# polar_bear.net
KiCad netlist of a schematic drawn in EAGLE
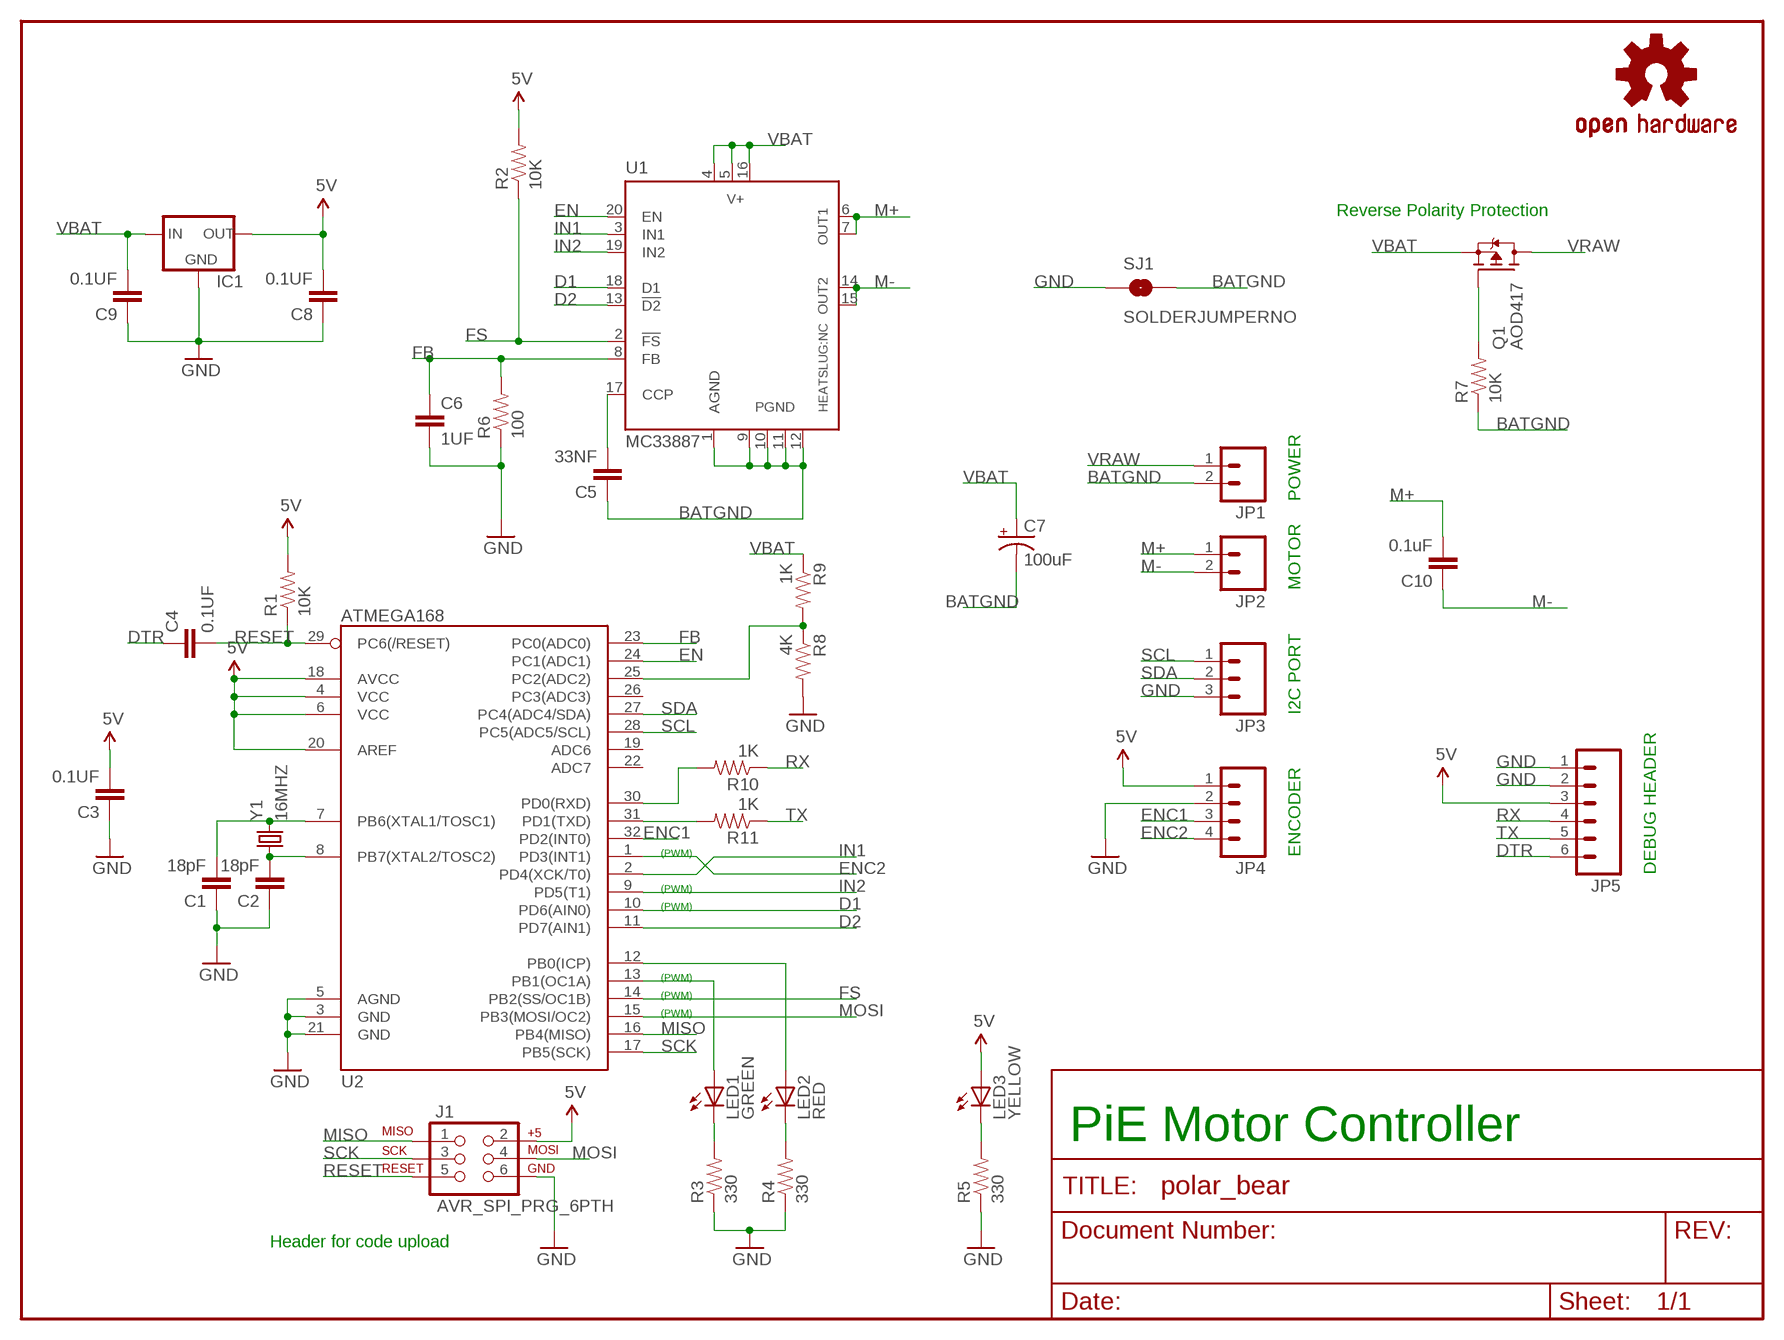
[diagram p0: schematic, sheet 1]

(export (version "E")
  (design (tool "Eeschema 10.0.6"))
  (components
    (comp (ref "C1")
      (value "18pF")
      (footprint "eagle-import:0805")
      (libsource (lib "eagle-import") (part "CAP0805"))
    )
    (comp (ref "C2")
      (value "18pF")
      (footprint "eagle-import:0805")
      (libsource (lib "eagle-import") (part "CAP0805"))
    )
    (comp (ref "C3")
      (value "0.1UF")
      (footprint "eagle-import:0805")
      (libsource (lib "eagle-import") (part "CAP0805"))
    )
    (comp (ref "C4")
      (value "0.1UF")
      (footprint "eagle-import:0805")
      (libsource (lib "eagle-import") (part "CAP0805"))
    )
    (comp (ref "C5")
      (value "33NF")
      (footprint "eagle-import:0805")
      (libsource (lib "eagle-import") (part "CAP0805"))
    )
    (comp (ref "C6")
      (value "1UF")
      (footprint "eagle-import:0805")
      (libsource (lib "eagle-import") (part "CAP0805"))
    )
    (comp (ref "C7")
      (value "100uF")
      (footprint "eagle-import:CPOL-RADIAL-100UF-25V")
      (libsource (lib "eagle-import") (part "CAP_POLPTH1"))
    )
    (comp (ref "C8")
      (value "0.1UF")
      (footprint "eagle-import:0805")
      (libsource (lib "eagle-import") (part "CAP0805"))
    )
    (comp (ref "C9")
      (value "0.1UF")
      (footprint "eagle-import:0805")
      (libsource (lib "eagle-import") (part "CAP0805"))
    )
    (comp (ref "C10")
      (value "0.1uF")
      (footprint "eagle-import:0805")
      (libsource (lib "eagle-import") (part "CAP0805"))
    )
    (comp (ref "IC1")
      (value "V_REG_78XXTO-92")
      (footprint "eagle-import:TO-92")
      (libsource (lib "eagle-import") (part "V_REG_78XXTO-92"))
    )
    (comp (ref "J1")
      (value "AVR_SPI_PRG_6PTH")
      (footprint "eagle-import:2X3")
      (libsource (lib "eagle-import") (part "AVR_SPI_PRG_6PTH"))
    )
    (comp (ref "JP1")
      (value "M02PTH4")
      (footprint "eagle-import:1X02_XTRA_BIG")
      (libsource (lib "eagle-import") (part "M02PTH4"))
    )
    (comp (ref "JP2")
      (value "M02PTH4")
      (footprint "eagle-import:1X02_XTRA_BIG")
      (libsource (lib "eagle-import") (part "M02PTH4"))
    )
    (comp (ref "JP3")
      (value "M03POLAR")
      (footprint "eagle-import:MOLEX-1X3")
      (libsource (lib "eagle-import") (part "M03POLAR"))
    )
    (comp (ref "JP4")
      (value "M04POLAR")
      (footprint "eagle-import:MOLEX-1X4")
      (libsource (lib "eagle-import") (part "M04POLAR"))
    )
    (comp (ref "JP5")
      (value "M06SIP")
      (footprint "eagle-import:1X06")
      (libsource (lib "eagle-import") (part "M06SIP"))
    )
    (comp (ref "LED1")
      (value "GREEN")
      (footprint "eagle-import:LED-1206")
      (libsource (lib "eagle-import") (part "LED1206"))
    )
    (comp (ref "LED2")
      (value "RED")
      (footprint "eagle-import:LED-1206")
      (libsource (lib "eagle-import") (part "LED1206"))
    )
    (comp (ref "LED3")
      (value "YELLOW")
      (footprint "eagle-import:LED-1206")
      (libsource (lib "eagle-import") (part "LED1206"))
    )
    (comp (ref "Q1")
      (value "AOD417")
      (footprint "eagle-import:TO252")
      (libsource (lib "eagle-import") (part "AOD417"))
    )
    (comp (ref "R1")
      (value "10K")
      (footprint "eagle-import:0805")
      (libsource (lib "eagle-import") (part "RESISTOR0805-RES"))
    )
    (comp (ref "R2")
      (value "10K")
      (footprint "eagle-import:0805")
      (libsource (lib "eagle-import") (part "RESISTOR0805-RES"))
    )
    (comp (ref "R3")
      (value "330")
      (footprint "eagle-import:0805")
      (libsource (lib "eagle-import") (part "RESISTOR0805-RES"))
    )
    (comp (ref "R4")
      (value "330")
      (footprint "eagle-import:0805")
      (libsource (lib "eagle-import") (part "RESISTOR0805-RES"))
    )
    (comp (ref "R5")
      (value "330")
      (footprint "eagle-import:0805")
      (libsource (lib "eagle-import") (part "RESISTOR0805-RES"))
    )
    (comp (ref "R6")
      (value "100")
      (footprint "eagle-import:0805")
      (libsource (lib "eagle-import") (part "RESISTOR0805-RES"))
    )
    (comp (ref "R7")
      (value "10K")
      (footprint "eagle-import:0805")
      (libsource (lib "eagle-import") (part "RESISTOR0805-RES"))
    )
    (comp (ref "R8")
      (value "4K")
      (footprint "eagle-import:0805")
      (libsource (lib "eagle-import") (part "RESISTOR0805-RES"))
    )
    (comp (ref "R9")
      (value "1K")
      (footprint "eagle-import:0805")
      (libsource (lib "eagle-import") (part "RESISTOR0805-RES"))
    )
    (comp (ref "R10")
      (value "1K")
      (footprint "eagle-import:0805")
      (libsource (lib "eagle-import") (part "RESISTOR0805-RES"))
    )
    (comp (ref "R11")
      (value "1K")
      (footprint "eagle-import:0805")
      (libsource (lib "eagle-import") (part "RESISTOR0805-RES"))
    )
    (comp (ref "SJ1")
      (value "SOLDERJUMPERNO")
      (footprint "eagle-import:SJ_2S-NO")
      (libsource (lib "eagle-import") (part "SOLDERJUMPERNO"))
    )
    (comp (ref "U$12")
      (value "OSHW-LOGOS")
      (footprint "eagle-import:OSHW-LOGO-S")
      (libsource (lib "eagle-import") (part "OSHW-LOGOS"))
    )
    (comp (ref "U1")
      (value "MC33887")
      (footprint "eagle-import:HSOP-20")
      (libsource (lib "eagle-import") (part "MC33887"))
    )
    (comp (ref "U2")
      (value "ATMEGA168")
      (footprint "eagle-import:TQFP32-08")
      (libsource (lib "eagle-import") (part "ATMEGA168"))
    )
    (comp (ref "Y1")
      (value "16MHZ")
      (footprint "eagle-import:HC49US")
      (libsource (lib "eagle-import") (part "CRYSTALHC49US"))
    )
  )
  (nets
    (net (code "1") (name "/BATGND") (class "Default")
      (node (ref "C5") (pin "1") (pinfunction "1_1") (pintype "passive"))
      (node (ref "C7") (pin "2") (pinfunction "-_2") (pintype "passive"))
      (node (ref "JP1") (pin "2") (pinfunction "2_2") (pintype "passive"))
      (node (ref "R7") (pin "1") (pinfunction "1_1") (pintype "passive"))
      (node (ref "SJ1") (pin "2") (pinfunction "2_2") (pintype "passive"))
      (node (ref "U1") (pin "1") (pinfunction "AGND_1") (pintype "power_in"))
      (node (ref "U1") (pin "10") (pinfunction "PGND_10") (pintype "power_in"))
      (node (ref "U1") (pin "11") (pinfunction "PGND_11") (pintype "power_in"))
      (node (ref "U1") (pin "12") (pinfunction "PGND_12") (pintype "power_in"))
      (node (ref "U1") (pin "9") (pinfunction "PGND_9") (pintype "power_in"))
    )
    (net (code "2") (name "/D1") (class "Default")
      (node (ref "U1") (pin "18") (pinfunction "D1_18") (pintype "input"))
      (node (ref "U2") (pin "10") (pinfunction "PD6(AIN0)_10") (pintype "bidirectional"))
    )
    (net (code "3") (name "/D2") (class "Default")
      (node (ref "U1") (pin "13") (pinfunction "~{D2}_13") (pintype "input"))
      (node (ref "U2") (pin "11") (pinfunction "PD7(AIN1)_11") (pintype "bidirectional"))
    )
    (net (code "4") (name "/DTR") (class "Default")
      (node (ref "C4") (pin "1") (pinfunction "1_1") (pintype "passive"))
      (node (ref "JP5") (pin "6") (pinfunction "6_6") (pintype "passive"))
    )
    (net (code "5") (name "/EN") (class "Default")
      (node (ref "U1") (pin "20") (pinfunction "EN_20") (pintype "input"))
      (node (ref "U2") (pin "24") (pinfunction "PC1(ADC1)_24") (pintype "bidirectional"))
    )
    (net (code "6") (name "/ENC1") (class "Default")
      (node (ref "JP4") (pin "3") (pinfunction "3_3") (pintype "passive"))
      (node (ref "U2") (pin "32") (pinfunction "PD2(INT0)_32") (pintype "bidirectional"))
    )
    (net (code "7") (name "/ENC2") (class "Default")
      (node (ref "JP4") (pin "4") (pinfunction "4_4") (pintype "passive"))
      (node (ref "U2") (pin "1") (pinfunction "PD3(INT1)_1") (pintype "bidirectional"))
    )
    (net (code "8") (name "/FB") (class "Default")
      (node (ref "C6") (pin "1") (pinfunction "1_1") (pintype "passive"))
      (node (ref "R6") (pin "2") (pinfunction "2_2") (pintype "passive"))
      (node (ref "U1") (pin "8") (pinfunction "FB_8") (pintype "output"))
      (node (ref "U2") (pin "23") (pinfunction "PC0(ADC0)_23") (pintype "bidirectional"))
    )
    (net (code "9") (name "/FS") (class "Default")
      (node (ref "R2") (pin "1") (pinfunction "1_1") (pintype "passive"))
      (node (ref "U1") (pin "2") (pinfunction "~{FS}_2") (pintype "open_collector"))
      (node (ref "U2") (pin "14") (pinfunction "PB2(SS/OC1B)_14") (pintype "bidirectional"))
    )
    (net (code "10") (name "/IN1") (class "Default")
      (node (ref "U1") (pin "3") (pinfunction "IN1_3") (pintype "input"))
      (node (ref "U2") (pin "2") (pinfunction "PD4(XCK/T0)_2") (pintype "bidirectional"))
    )
    (net (code "11") (name "/IN2") (class "Default")
      (node (ref "U1") (pin "19") (pinfunction "IN2_19") (pintype "input"))
      (node (ref "U2") (pin "9") (pinfunction "PD5(T1)_9") (pintype "bidirectional"))
    )
    (net (code "12") (name "/M+") (class "Default")
      (node (ref "C10") (pin "2") (pinfunction "2_2") (pintype "passive"))
      (node (ref "JP2") (pin "1") (pinfunction "1_1") (pintype "passive"))
      (node (ref "U1") (pin "6") (pinfunction "OUT1_6") (pintype "output"))
      (node (ref "U1") (pin "7") (pinfunction "OUT1_7") (pintype "output"))
    )
    (net (code "13") (name "/M-") (class "Default")
      (node (ref "C10") (pin "1") (pinfunction "1_1") (pintype "passive"))
      (node (ref "JP2") (pin "2") (pinfunction "2_2") (pintype "passive"))
      (node (ref "U1") (pin "14") (pinfunction "OUT2_14") (pintype "output"))
      (node (ref "U1") (pin "15") (pinfunction "OUT2_15") (pintype "output"))
    )
    (net (code "14") (name "/MISO") (class "Default")
      (node (ref "J1") (pin "1") (pinfunction "1_1") (pintype "passive"))
      (node (ref "U2") (pin "16") (pinfunction "PB4(MISO)_16") (pintype "bidirectional"))
    )
    (net (code "15") (name "/MOSI") (class "Default")
      (node (ref "J1") (pin "4") (pinfunction "4_4") (pintype "passive"))
      (node (ref "U2") (pin "15") (pinfunction "PB3(MOSI/OC2)_15") (pintype "bidirectional"))
    )
    (net (code "16") (name "/RESET") (class "Default")
      (node (ref "C4") (pin "2") (pinfunction "2_2") (pintype "passive"))
      (node (ref "J1") (pin "5") (pinfunction "5_5") (pintype "passive"))
      (node (ref "R1") (pin "1") (pinfunction "1_1") (pintype "passive"))
      (node (ref "U2") (pin "29") (pinfunction "PC6(/RESET)_29") (pintype "bidirectional"))
    )
    (net (code "17") (name "/RX") (class "Default")
      (node (ref "JP5") (pin "4") (pinfunction "4_4") (pintype "passive"))
      (node (ref "R10") (pin "1") (pinfunction "1_1") (pintype "passive"))
    )
    (net (code "18") (name "/SCK") (class "Default")
      (node (ref "J1") (pin "3") (pinfunction "3_3") (pintype "passive"))
      (node (ref "U2") (pin "17") (pinfunction "PB5(SCK)_17") (pintype "bidirectional"))
    )
    (net (code "19") (name "/SCL") (class "Default")
      (node (ref "JP3") (pin "1") (pinfunction "1_1") (pintype "passive"))
      (node (ref "U2") (pin "28") (pinfunction "PC5(ADC5/SCL)_28") (pintype "bidirectional"))
    )
    (net (code "20") (name "/SDA") (class "Default")
      (node (ref "JP3") (pin "2") (pinfunction "2_2") (pintype "passive"))
      (node (ref "U2") (pin "27") (pinfunction "PC4(ADC4/SDA)_27") (pintype "bidirectional"))
    )
    (net (code "21") (name "/TX") (class "Default")
      (node (ref "JP5") (pin "5") (pinfunction "5_5") (pintype "passive"))
      (node (ref "R11") (pin "1") (pinfunction "1_1") (pintype "passive"))
    )
    (net (code "22") (name "/VBAT") (class "Default")
      (node (ref "C7") (pin "1") (pinfunction "+_1") (pintype "passive"))
      (node (ref "C9") (pin "2") (pinfunction "2_2") (pintype "passive"))
      (node (ref "IC1") (pin "2") (pinfunction "IN_2") (pintype "input"))
      (node (ref "Q1") (pin "2") (pinfunction "S_2") (pintype "passive"))
      (node (ref "R9") (pin "1") (pinfunction "1_1") (pintype "passive"))
      (node (ref "U1") (pin "16") (pinfunction "V+_16") (pintype "power_in"))
      (node (ref "U1") (pin "4") (pinfunction "V+_4") (pintype "power_in"))
      (node (ref "U1") (pin "5") (pinfunction "V+_5") (pintype "power_in"))
    )
    (net (code "23") (name "/VRAW") (class "Default")
      (node (ref "JP1") (pin "1") (pinfunction "1_1") (pintype "passive"))
      (node (ref "Q1") (pin "3") (pinfunction "D_3") (pintype "passive"))
    )
    (net (code "24") (name "5V") (class "Default")
      (node (ref "C3") (pin "2") (pinfunction "2_2") (pintype "passive"))
      (node (ref "C8") (pin "2") (pinfunction "2_2") (pintype "passive"))
      (node (ref "IC1") (pin "3") (pinfunction "OUT_3") (pintype "output"))
      (node (ref "J1") (pin "2") (pinfunction "2_2") (pintype "passive"))
      (node (ref "JP4") (pin "1") (pinfunction "1_1") (pintype "passive"))
      (node (ref "JP5") (pin "3") (pinfunction "3_3") (pintype "passive"))
      (node (ref "LED3") (pin "A") (pinfunction "A_A") (pintype "passive"))
      (node (ref "R1") (pin "2") (pinfunction "2_2") (pintype "passive"))
      (node (ref "R2") (pin "2") (pinfunction "2_2") (pintype "passive"))
      (node (ref "U2") (pin "18") (pinfunction "AVCC_18") (pintype "bidirectional"))
      (node (ref "U2") (pin "20") (pinfunction "AREF_20") (pintype "bidirectional"))
      (node (ref "U2") (pin "4") (pinfunction "VCC_4") (pintype "bidirectional"))
      (node (ref "U2") (pin "6") (pinfunction "VCC_6") (pintype "bidirectional"))
    )
    (net (code "25") (name "GND") (class "Default")
      (node (ref "C1") (pin "1") (pinfunction "1_1") (pintype "passive"))
      (node (ref "C2") (pin "1") (pinfunction "1_1") (pintype "passive"))
      (node (ref "C3") (pin "1") (pinfunction "1_1") (pintype "passive"))
      (node (ref "C6") (pin "2") (pinfunction "2_2") (pintype "passive"))
      (node (ref "C8") (pin "1") (pinfunction "1_1") (pintype "passive"))
      (node (ref "C9") (pin "1") (pinfunction "1_1") (pintype "passive"))
      (node (ref "IC1") (pin "1") (pinfunction "GND_1") (pintype "input"))
      (node (ref "J1") (pin "6") (pinfunction "6_6") (pintype "passive"))
      (node (ref "JP3") (pin "3") (pinfunction "3_3") (pintype "passive"))
      (node (ref "JP4") (pin "2") (pinfunction "2_2") (pintype "passive"))
      (node (ref "JP5") (pin "1") (pinfunction "1_1") (pintype "passive"))
      (node (ref "JP5") (pin "2") (pinfunction "2_2") (pintype "passive"))
      (node (ref "R3") (pin "1") (pinfunction "1_1") (pintype "passive"))
      (node (ref "R4") (pin "1") (pinfunction "1_1") (pintype "passive"))
      (node (ref "R5") (pin "1") (pinfunction "1_1") (pintype "passive"))
      (node (ref "R6") (pin "1") (pinfunction "1_1") (pintype "passive"))
      (node (ref "R8") (pin "2") (pinfunction "2_2") (pintype "passive"))
      (node (ref "SJ1") (pin "1") (pinfunction "1_1") (pintype "passive"))
      (node (ref "U2") (pin "21") (pinfunction "GND_21") (pintype "bidirectional"))
      (node (ref "U2") (pin "3") (pinfunction "GND_3") (pintype "bidirectional"))
      (node (ref "U2") (pin "5") (pinfunction "AGND_5") (pintype "bidirectional"))
    )
    (net (code "26") (name "Net-(LED1-PadC)") (class "Default")
      (node (ref "LED1") (pin "C") (pinfunction "C_C") (pintype "passive"))
      (node (ref "R3") (pin "2") (pinfunction "2_2") (pintype "passive"))
    )
    (net (code "27") (name "Net-(LED2-PadC)") (class "Default")
      (node (ref "LED2") (pin "C") (pinfunction "C_C") (pintype "passive"))
      (node (ref "R4") (pin "2") (pinfunction "2_2") (pintype "passive"))
    )
    (net (code "28") (name "Net-(LED3-PadC)") (class "Default")
      (node (ref "LED3") (pin "C") (pinfunction "C_C") (pintype "passive"))
      (node (ref "R5") (pin "2") (pinfunction "2_2") (pintype "passive"))
    )
    (net (code "29") (name "Net-(Q1-G)") (class "Default")
      (node (ref "Q1") (pin "1") (pinfunction "G_1") (pintype "passive"))
      (node (ref "R7") (pin "2") (pinfunction "2_2") (pintype "passive"))
    )
    (net (code "30") (name "Net-(U1-CCP)") (class "Default")
      (node (ref "C5") (pin "2") (pinfunction "2_2") (pintype "passive"))
      (node (ref "U1") (pin "17") (pinfunction "CCP_17") (pintype "passive"))
    )
    (net (code "31") (name "Net-(U2-PB0(ICP))") (class "Default")
      (node (ref "LED2") (pin "A") (pinfunction "A_A") (pintype "passive"))
      (node (ref "U2") (pin "12") (pinfunction "PB0(ICP)_12") (pintype "bidirectional"))
    )
    (net (code "32") (name "Net-(U2-PB1(OC1A))") (class "Default")
      (node (ref "LED1") (pin "A") (pinfunction "A_A") (pintype "passive"))
      (node (ref "U2") (pin "13") (pinfunction "PB1(OC1A)_13") (pintype "bidirectional"))
    )
    (net (code "33") (name "Net-(U2-PB6(XTAL1{slash}TOSC1))") (class "Default")
      (node (ref "C1") (pin "2") (pinfunction "2_2") (pintype "passive"))
      (node (ref "U2") (pin "7") (pinfunction "PB6(XTAL1/TOSC1)_7") (pintype "bidirectional"))
      (node (ref "Y1") (pin "2") (pinfunction "2_2") (pintype "passive"))
    )
    (net (code "34") (name "Net-(U2-PB7(XTAL2{slash}TOSC2))") (class "Default")
      (node (ref "C2") (pin "2") (pinfunction "2_2") (pintype "passive"))
      (node (ref "U2") (pin "8") (pinfunction "PB7(XTAL2/TOSC2)_8") (pintype "bidirectional"))
      (node (ref "Y1") (pin "1") (pinfunction "1_1") (pintype "passive"))
    )
    (net (code "35") (name "Net-(U2-PC2(ADC2))") (class "Default")
      (node (ref "R8") (pin "1") (pinfunction "1_1") (pintype "passive"))
      (node (ref "R9") (pin "2") (pinfunction "2_2") (pintype "passive"))
      (node (ref "U2") (pin "25") (pinfunction "PC2(ADC2)_25") (pintype "bidirectional"))
    )
    (net (code "36") (name "Net-(U2-PD0(RXD))") (class "Default")
      (node (ref "R10") (pin "2") (pinfunction "2_2") (pintype "passive"))
      (node (ref "U2") (pin "30") (pinfunction "PD0(RXD)_30") (pintype "bidirectional"))
    )
    (net (code "37") (name "Net-(U2-PD1(TXD))") (class "Default")
      (node (ref "R11") (pin "2") (pinfunction "2_2") (pintype "passive"))
      (node (ref "U2") (pin "31") (pinfunction "PD1(TXD)_31") (pintype "bidirectional"))
    )
    (net (code "38") (name "unconnected-(U2-ADC6-Pad19)") (class "Default")
      (node (ref "U2") (pin "19") (pinfunction "ADC6_19") (pintype "bidirectional"))
    )
    (net (code "39") (name "unconnected-(U2-ADC7-Pad22)") (class "Default")
      (node (ref "U2") (pin "22") (pinfunction "ADC7_22") (pintype "bidirectional"))
    )
    (net (code "40") (name "unconnected-(U2-PC3(ADC3)-Pad26)") (class "Default")
      (node (ref "U2") (pin "26") (pinfunction "PC3(ADC3)_26") (pintype "bidirectional"))
    )
  )
)
